# POWER.net
KiCad netlist of a schematic drawn in Altium Designer
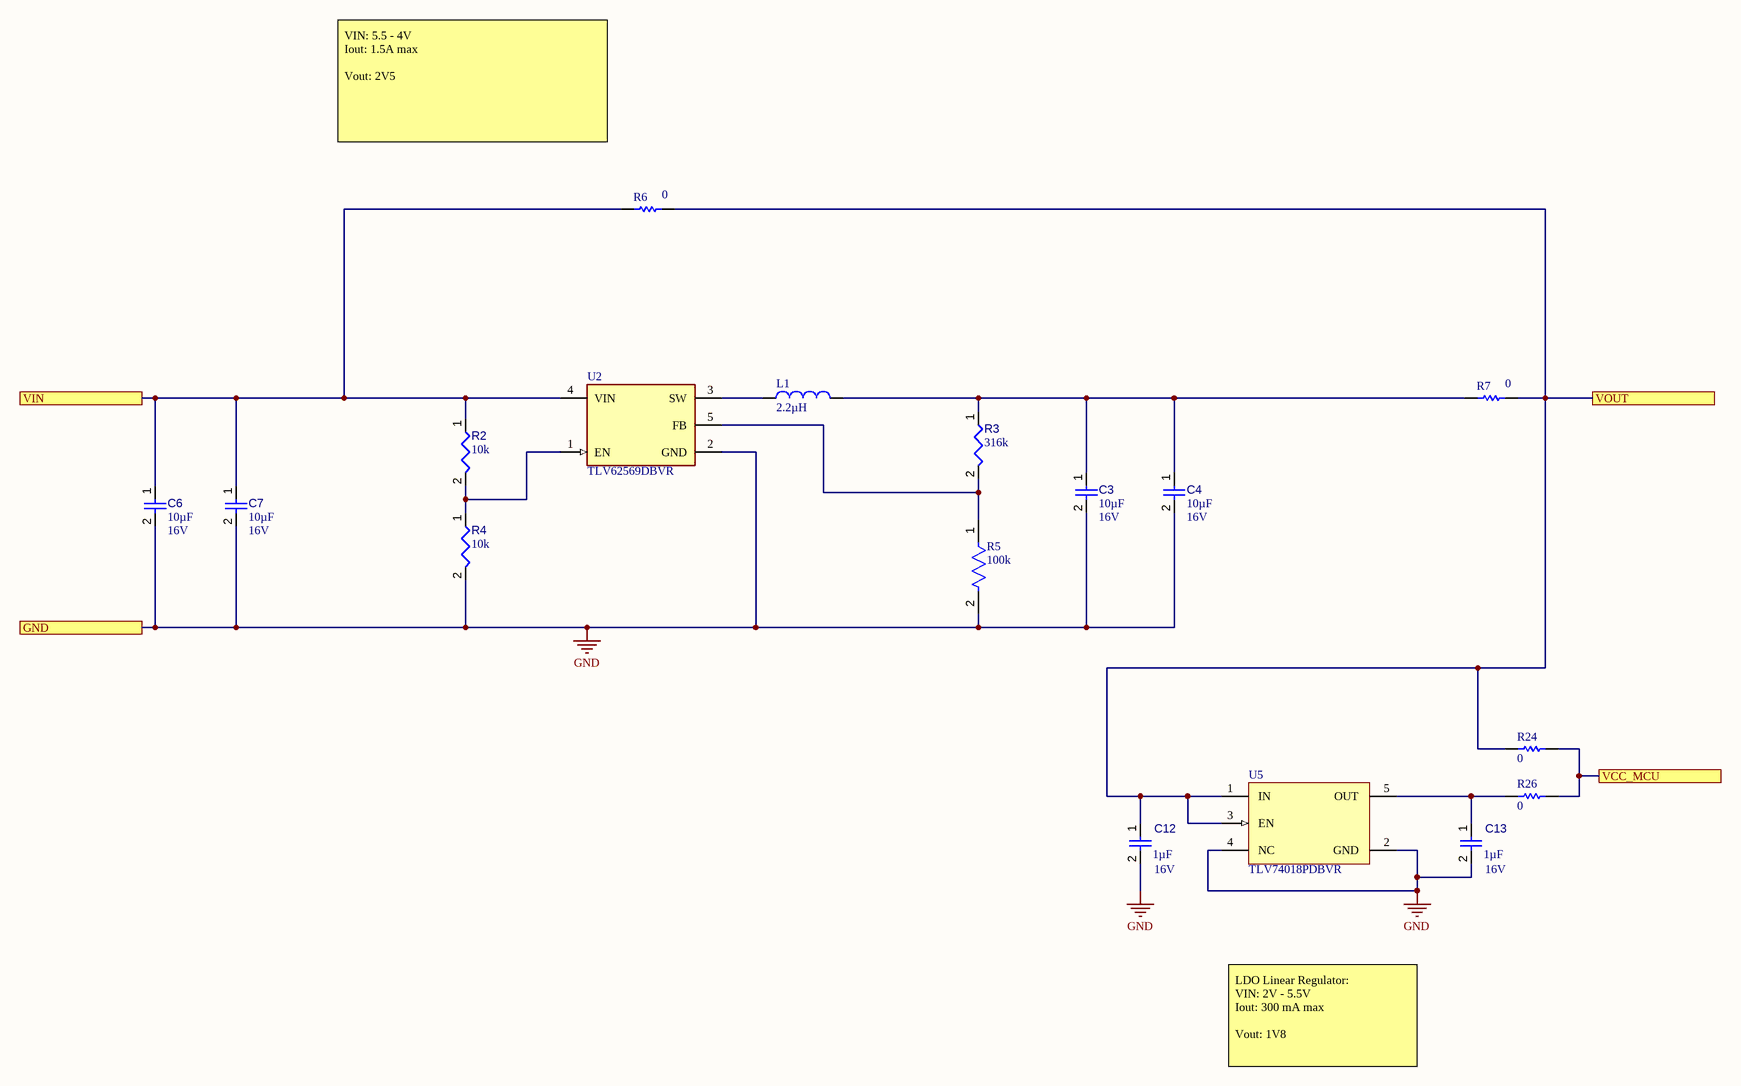
[diagram p0: POWER.SchDoc]

(export (version "E")
  (design (tool "Eeschema 10.0.6"))
  (components
    (comp (ref "C3")
      (value "10µF")
      (footprint "CAPC1608X09N")
      (fields (field (name "VOLTAGE RATING") "16V") (field (name "Comment") "CL10A106MO8NQNC"))
      (libsource (lib "Global Health Labs, Inc") (part "CAP-NP-2"))
    )
    (comp (ref "C4")
      (value "10µF")
      (footprint "CAPC1608X09N")
      (fields (field (name "VOLTAGE RATING") "16V") (field (name "Comment") "CL10A106MO8NQNC"))
      (libsource (lib "Global Health Labs, Inc") (part "CAP-NP-2"))
    )
    (comp (ref "C6")
      (value "10µF")
      (footprint "CAPC1608X09N")
      (fields (field (name "VOLTAGE RATING") "16V") (field (name "Comment") "CL10A106MO8NQNC"))
      (libsource (lib "Global Health Labs, Inc") (part "CAP-NP-2"))
    )
    (comp (ref "C7")
      (value "10µF")
      (footprint "CAPC1608X09N")
      (fields (field (name "VOLTAGE RATING") "16V") (field (name "Comment") "CL10A106MO8NQNC"))
      (libsource (lib "Global Health Labs, Inc") (part "CAP-NP-2"))
    )
    (comp (ref "C12")
      (value "1µF")
      (footprint "CAPC1005X55X25ML05T10")
      (description "Chip Capacitor, 1 uF, +/- 10%, 16V, 0402 (1005 Metric)")
      (fields
        (field (name "TOLERANCE") "10%")
        (field (name "VOLTAGE RATING") "16V")
        (field (name "Comment") "Capacitor 1 uF +/- 10% 16V 0402")
      )
      (libsource (lib "Global Health Labs, Inc") (part "CAP-NP-2"))
    )
    (comp (ref "C13")
      (value "1µF")
      (footprint "CAPC1005X55X25ML05T10")
      (description "Chip Capacitor, 1 uF, +/- 10%, 16V, 0402 (1005 Metric)")
      (fields
        (field (name "TOLERANCE") "10%")
        (field (name "VOLTAGE RATING") "16V")
        (field (name "Comment") "Capacitor 1 uF +/- 10% 16V 0402")
      )
      (libsource (lib "Global Health Labs, Inc") (part "CAP-NP-2"))
    )
    (comp (ref "L1")
      (value "2.2µH")
      (footprint "INDC5050X40N")
      (description "Shielded wirewound inductor, 2.2uH, 20%, 3.95A, 17 mohm DCR")
      (fields (field (name "TOLERANCE") "20%") (field (name "Comment") "CMLW5040S2R2MST"))
      (libsource (lib "Global Health Labs, Inc") (part "IND-2"))
    )
    (comp (ref "R2")
      (value "10k")
      (footprint "RESC0402(1005)_L")
      (description "Chip Resistor, 10 kOhms, +/-1 %, 63 mW, -55 to 125 degC, 0402")
      (fields (field (name "POWER") "63mW") (field (name "TOLERANCE") "1%"))
      (libsource (lib "") (part "RES-2_1"))
    )
    (comp (ref "R3")
      (value "316k")
      (footprint "RESC0402(1005)_L")
      (description "Chip Resistor, 316 kOhms, +/-1 %, 63 mW, -55 to 155 degC, 0402")
      (fields (field (name "POWER") "63mW") (field (name "TOLERANCE") "1%"))
      (libsource (lib "") (part "RES-2_1"))
    )
    (comp (ref "R4")
      (value "10k")
      (footprint "RESC0402(1005)_L")
      (description "Chip Resistor, 10 kOhms, +/-1 %, 63 mW, -55 to 125 degC, 0402")
      (fields (field (name "POWER") "63mW") (field (name "TOLERANCE") "1%"))
      (libsource (lib "") (part "RES-2_1"))
    )
    (comp (ref "R5")
      (value "CRCW0402100KFKED")
      (footprint "FP-CRCW0402-e3-IPC_C")
      (description "RES Thick Film, 100kΩ, 1%, 0.063W, 100ppm/°C, 0402")
      (fields (field (name "RESISTANCE") "100k") (field (name "TOLERANCE") "1%"))
      (libsource (lib "Altium Content Vault") (part "1029c3af85768c4190bb7ad29bc67b5"))
    )
    (comp (ref "R6")
      (value "0")
      (footprint "RESC2013X50X35ML15T15")
      (description "Chip Resistor, 0 Ohm, +/- 1%, 125 mW, -55 to 155 degC, 0805 (2012 Metric)")
      (fields (field (name "TOLERANCE") "1%") (field (name "POWER") "125mW"))
      (libsource (lib "Global Health Labs, Inc") (part "RES-2"))
    )
    (comp (ref "R7")
      (value "0")
      (footprint "RESC2013X50X35ML15T15")
      (description "Chip Resistor, 0 Ohm, +/- 1%, 125 mW, -55 to 155 degC, 0805 (2012 Metric)")
      (fields (field (name "TOLERANCE") "1%") (field (name "POWER") "125mW"))
      (libsource (lib "Global Health Labs, Inc") (part "RES-2"))
    )
    (comp (ref "R24")
      (value "0")
      (footprint "RESC1608X55X25ML10T15")
      (description "Chip Resistor, 0 Ohm, 0.1 W, -55 to 155 degC, 0603 (1608 Metric)")
      (fields (field (name "POWER") "100mW") (field (name "TOLERANCE") "5%"))
      (libsource (lib "Global Health Labs, Inc") (part "RES-2"))
    )
    (comp (ref "R26")
      (value "0")
      (footprint "RESC1608X55X25ML10T15")
      (description "Chip Resistor, 0 Ohm, 0.1 W, -55 to 155 degC, 0603 (1608 Metric)")
      (fields (field (name "POWER") "100mW") (field (name "TOLERANCE") "5%"))
      (libsource (lib "Global Health Labs, Inc") (part "RES-2"))
    )
    (comp (ref "U2")
      (value "TLV62569DBVR")
      (footprint "FP-DBV0005A-IPC_B")
      (description "Switching Regulator, 2A, 1500kHz Switching Freq-Max, PDSO5")
      (libsource (lib "Global Health Labs, Inc") (part "f8671745ee5fb9a493b385c735b730b"))
    )
    (comp (ref "U5")
      (value "TLV74018PDBVR")
      (footprint "DBV0005A_MFG")
      (description "IC REG LINEAR 1.8V 300MA SOT23-5")
      (libsource (lib "Global Health Labs, Inc") (part "9444cdc507fe29f20f0adc9980b4e13"))
    )
  )
  (nets
    (net (code "1") (name "/VCC_MCU") (class "Default")
      (node (ref "R24") (pin "2") (pinfunction "2_2") (pintype "passive"))
      (node (ref "R26") (pin "2") (pinfunction "2_2") (pintype "passive"))
    )
    (net (code "2") (name "/VIN") (class "Default")
      (node (ref "C6") (pin "1") (pinfunction "1_1") (pintype "passive"))
      (node (ref "C7") (pin "1") (pinfunction "1_1") (pintype "passive"))
      (node (ref "R2") (pin "1") (pinfunction "1_1") (pintype "passive"))
      (node (ref "R6") (pin "1") (pinfunction "1_1") (pintype "passive"))
      (node (ref "U2") (pin "4") (pinfunction "VIN_4") (pintype "power_in"))
    )
    (net (code "3") (name "/VOUT") (class "Default")
      (node (ref "C12") (pin "1") (pinfunction "1_1") (pintype "passive"))
      (node (ref "R24") (pin "1") (pinfunction "1_1") (pintype "passive"))
      (node (ref "R6") (pin "2") (pinfunction "2_2") (pintype "passive"))
      (node (ref "R7") (pin "2") (pinfunction "2_2") (pintype "passive"))
      (node (ref "U5") (pin "1") (pinfunction "IN_1") (pintype "power_in"))
      (node (ref "U5") (pin "3") (pinfunction "EN_3") (pintype "input"))
    )
    (net (code "4") (name "GND") (class "Default")
      (node (ref "C12") (pin "2") (pinfunction "2_2") (pintype "passive"))
      (node (ref "C13") (pin "2") (pinfunction "2_2") (pintype "passive"))
      (node (ref "C3") (pin "2") (pinfunction "2_2") (pintype "passive"))
      (node (ref "C4") (pin "2") (pinfunction "2_2") (pintype "passive"))
      (node (ref "C6") (pin "2") (pinfunction "2_2") (pintype "passive"))
      (node (ref "C7") (pin "2") (pinfunction "2_2") (pintype "passive"))
      (node (ref "R4") (pin "2") (pinfunction "2_2") (pintype "passive"))
      (node (ref "R5") (pin "2") (pinfunction "2_2") (pintype "passive"))
      (node (ref "U2") (pin "2") (pinfunction "GND_2") (pintype "power_in"))
      (node (ref "U5") (pin "2") (pinfunction "GND_2") (pintype "power_in"))
      (node (ref "U5") (pin "4") (pinfunction "NC_4") (pintype "passive"))
    )
    (net (code "5") (name "Net-(C3-Pad1)") (class "Default")
      (node (ref "C3") (pin "1") (pinfunction "1_1") (pintype "passive"))
      (node (ref "C4") (pin "1") (pinfunction "1_1") (pintype "passive"))
      (node (ref "L1") (pin "2") (pinfunction "2_2") (pintype "passive"))
      (node (ref "R3") (pin "1") (pinfunction "1_1") (pintype "passive"))
      (node (ref "R7") (pin "1") (pinfunction "1_1") (pintype "passive"))
    )
    (net (code "6") (name "Net-(U2-EN)") (class "Default")
      (node (ref "R2") (pin "2") (pinfunction "2_2") (pintype "passive"))
      (node (ref "R4") (pin "1") (pinfunction "1_1") (pintype "passive"))
      (node (ref "U2") (pin "1") (pinfunction "EN_1") (pintype "input"))
    )
    (net (code "7") (name "Net-(U2-FB)") (class "Default")
      (node (ref "R3") (pin "2") (pinfunction "2_2") (pintype "passive"))
      (node (ref "R5") (pin "1") (pinfunction "1_1") (pintype "passive"))
      (node (ref "U2") (pin "5") (pinfunction "FB_5") (pintype "passive"))
    )
    (net (code "8") (name "Net-(U2-SW)") (class "Default")
      (node (ref "L1") (pin "1") (pinfunction "1_1") (pintype "passive"))
      (node (ref "U2") (pin "3") (pinfunction "SW_3") (pintype "power_in"))
    )
    (net (code "9") (name "Net-(U5-OUT)") (class "Default")
      (node (ref "C13") (pin "1") (pinfunction "1_1") (pintype "passive"))
      (node (ref "R26") (pin "1") (pinfunction "1_1") (pintype "passive"))
      (node (ref "U5") (pin "5") (pinfunction "OUT_5") (pintype "passive"))
    )
  )
)
